# Patch_Panel.net
KiCad netlist of a schematic drawn in EAGLE
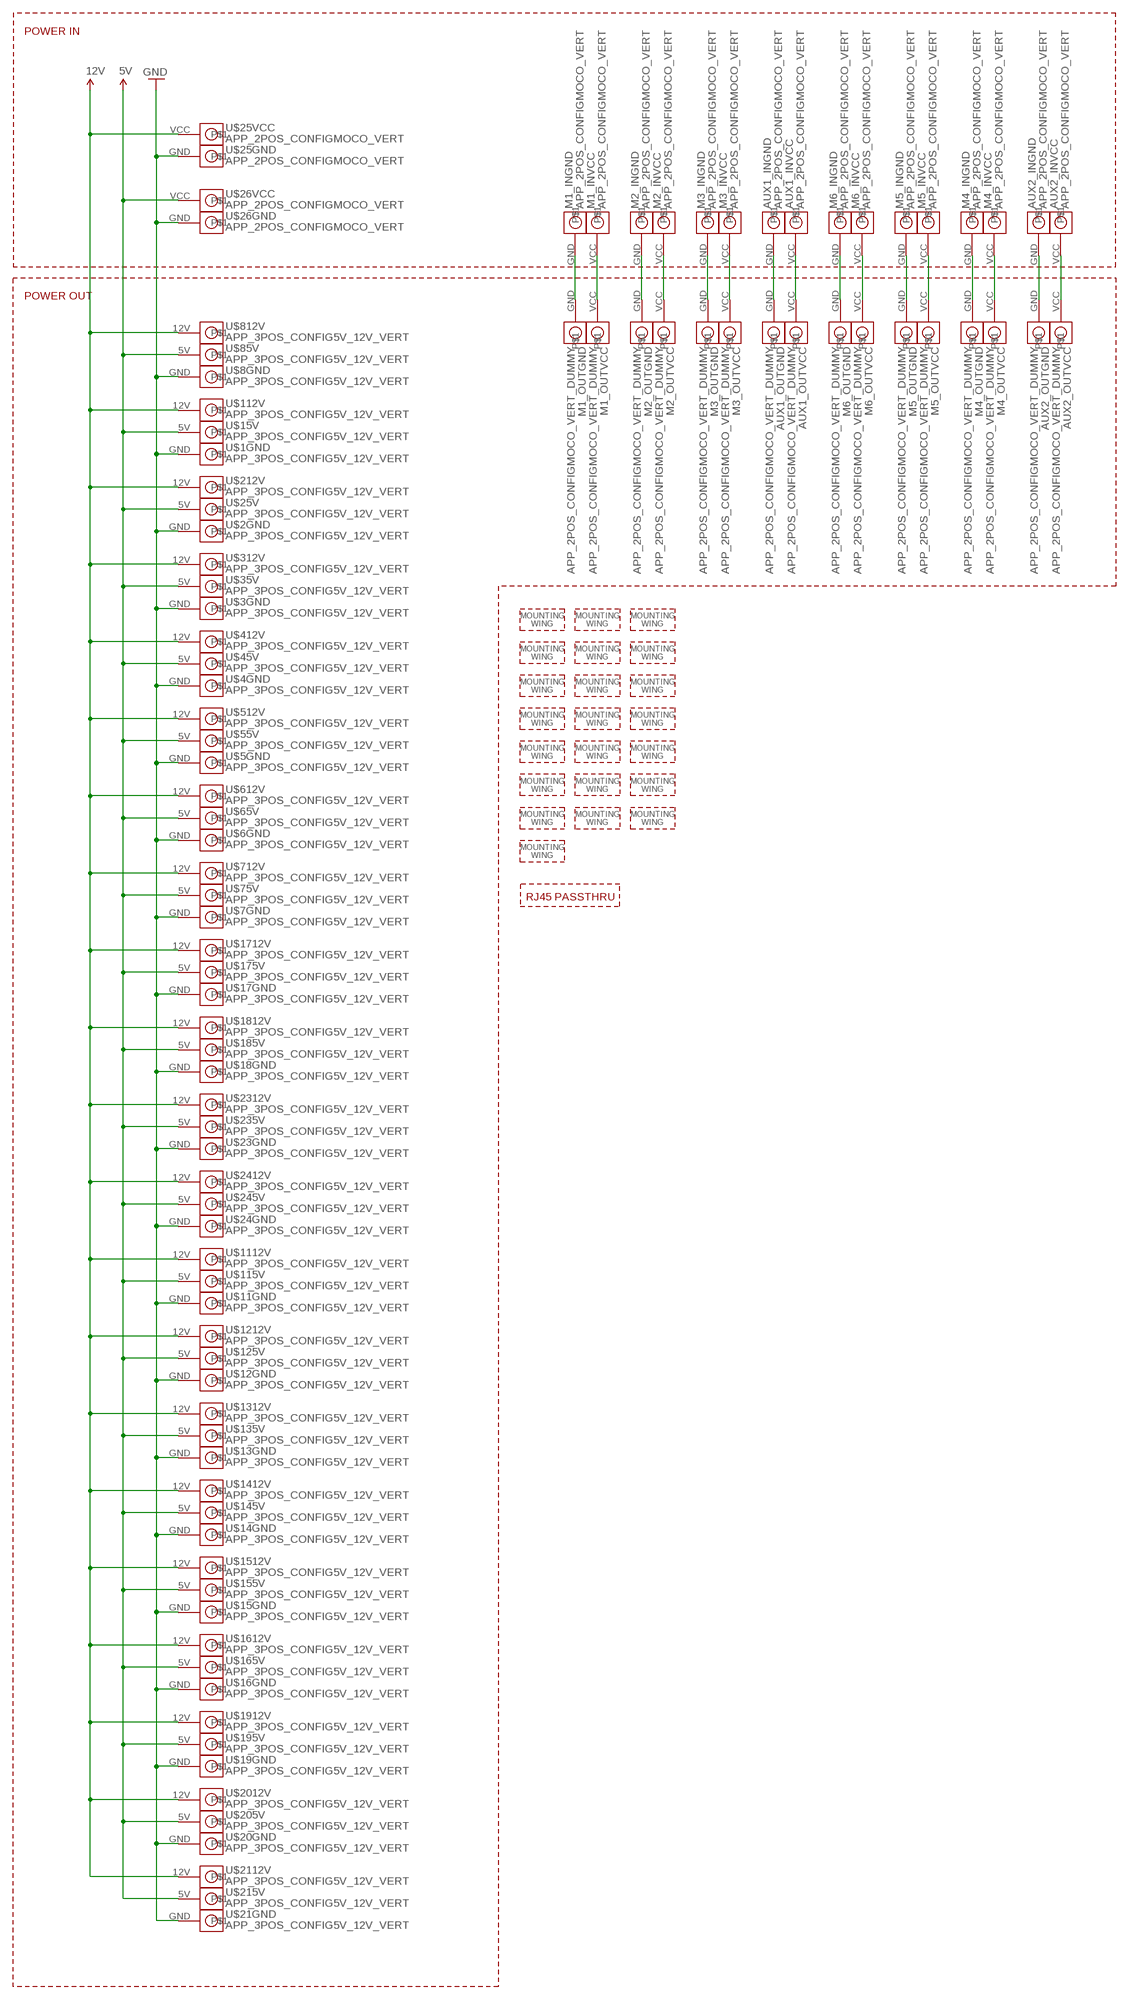
[diagram p0: schematic, sheet 1]

(export (version "E")
  (design (tool "Eeschema 10.0.6"))
  (components
    (comp (ref "AUX1_IN")
      (value "APP_2POS_CONFIGMOCO_VERT")
      (footprint "eagle-import:APP45_MOCO_VERT_CONFIG")
      (fields (field (name "COLOR1") "GREY"))
      (libsource (lib "eagle-import") (part "APP_2POS_CONFIGMOCO_VERT"))
    )
    (comp (ref "AUX1_OUT")
      (value "APP_2POS_CONFIGMOCO_VERT_DUMMY")
      (footprint "eagle-import:APP45_MOCO_VERT_CONFIG_DUMMY")
      (fields (field (name "COLOR1") "GREY"))
      (libsource (lib "eagle-import") (part "APP_2POS_CONFIGMOCO_VERT_DUMMY"))
    )
    (comp (ref "AUX2_IN")
      (value "APP_2POS_CONFIGMOCO_VERT")
      (footprint "eagle-import:APP45_MOCO_VERT_CONFIG")
      (fields (field (name "COLOR1") "GREY"))
      (libsource (lib "eagle-import") (part "APP_2POS_CONFIGMOCO_VERT"))
    )
    (comp (ref "AUX2_OUT")
      (value "APP_2POS_CONFIGMOCO_VERT_DUMMY")
      (footprint "eagle-import:APP45_MOCO_VERT_CONFIG_DUMMY")
      (fields (field (name "COLOR1") "GREY"))
      (libsource (lib "eagle-import") (part "APP_2POS_CONFIGMOCO_VERT_DUMMY"))
    )
    (comp (ref "M1_IN")
      (value "APP_2POS_CONFIGMOCO_VERT")
      (footprint "eagle-import:APP45_MOCO_VERT_CONFIG")
      (fields (field (name "COLOR1") "ORANGE"))
      (libsource (lib "eagle-import") (part "APP_2POS_CONFIGMOCO_VERT"))
    )
    (comp (ref "M1_OUT")
      (value "APP_2POS_CONFIGMOCO_VERT_DUMMY")
      (footprint "eagle-import:APP45_MOCO_VERT_CONFIG_DUMMY")
      (fields (field (name "COLOR1") "ORANGE"))
      (libsource (lib "eagle-import") (part "APP_2POS_CONFIGMOCO_VERT_DUMMY"))
    )
    (comp (ref "M2_IN")
      (value "APP_2POS_CONFIGMOCO_VERT")
      (footprint "eagle-import:APP45_MOCO_VERT_CONFIG")
      (fields (field (name "COLOR1") "WHITE"))
      (libsource (lib "eagle-import") (part "APP_2POS_CONFIGMOCO_VERT"))
    )
    (comp (ref "M2_OUT")
      (value "APP_2POS_CONFIGMOCO_VERT_DUMMY")
      (footprint "eagle-import:APP45_MOCO_VERT_CONFIG_DUMMY")
      (fields (field (name "COLOR1") "WHITE"))
      (libsource (lib "eagle-import") (part "APP_2POS_CONFIGMOCO_VERT_DUMMY"))
    )
    (comp (ref "M3_IN")
      (value "APP_2POS_CONFIGMOCO_VERT")
      (footprint "eagle-import:APP45_MOCO_VERT_CONFIG")
      (fields (field (name "COLOR1") "GREEN"))
      (libsource (lib "eagle-import") (part "APP_2POS_CONFIGMOCO_VERT"))
    )
    (comp (ref "M3_OUT")
      (value "APP_2POS_CONFIGMOCO_VERT_DUMMY")
      (footprint "eagle-import:APP45_MOCO_VERT_CONFIG_DUMMY")
      (fields (field (name "COLOR1") "GREEN"))
      (libsource (lib "eagle-import") (part "APP_2POS_CONFIGMOCO_VERT_DUMMY"))
    )
    (comp (ref "M4_IN")
      (value "APP_2POS_CONFIGMOCO_VERT")
      (footprint "eagle-import:APP45_MOCO_VERT_CONFIG")
      (fields (field (name "COLOR1") "PINK"))
      (libsource (lib "eagle-import") (part "APP_2POS_CONFIGMOCO_VERT"))
    )
    (comp (ref "M4_OUT")
      (value "APP_2POS_CONFIGMOCO_VERT_DUMMY")
      (footprint "eagle-import:APP45_MOCO_VERT_CONFIG_DUMMY")
      (fields (field (name "COLOR1") "PINK"))
      (libsource (lib "eagle-import") (part "APP_2POS_CONFIGMOCO_VERT_DUMMY"))
    )
    (comp (ref "M5_IN")
      (value "APP_2POS_CONFIGMOCO_VERT")
      (footprint "eagle-import:APP45_MOCO_VERT_CONFIG")
      (fields (field (name "COLOR1") "VIOLET"))
      (libsource (lib "eagle-import") (part "APP_2POS_CONFIGMOCO_VERT"))
    )
    (comp (ref "M5_OUT")
      (value "APP_2POS_CONFIGMOCO_VERT_DUMMY")
      (footprint "eagle-import:APP45_MOCO_VERT_CONFIG_DUMMY")
      (fields (field (name "COLOR1") "VIOLET"))
      (libsource (lib "eagle-import") (part "APP_2POS_CONFIGMOCO_VERT_DUMMY"))
    )
    (comp (ref "M6_IN")
      (value "APP_2POS_CONFIGMOCO_VERT")
      (footprint "eagle-import:APP45_MOCO_VERT_CONFIG")
      (fields (field (name "COLOR1") "BLUE"))
      (libsource (lib "eagle-import") (part "APP_2POS_CONFIGMOCO_VERT"))
    )
    (comp (ref "M6_OUT")
      (value "APP_2POS_CONFIGMOCO_VERT_DUMMY")
      (footprint "eagle-import:APP45_MOCO_VERT_CONFIG_DUMMY")
      (fields (field (name "COLOR1") "BLUE"))
      (libsource (lib "eagle-import") (part "APP_2POS_CONFIGMOCO_VERT_DUMMY"))
    )
    (comp (ref "U$1")
      (value "APP_3POS_CONFIG5V_12V_VERT")
      (footprint "eagle-import:APP45_5V_12V_VERT_CONFIG")
      (libsource (lib "eagle-import") (part "APP_3POS_CONFIG5V_12V_VERT"))
    )
    (comp (ref "U$2")
      (value "APP_3POS_CONFIG5V_12V_VERT")
      (footprint "eagle-import:APP45_5V_12V_VERT_CONFIG")
      (libsource (lib "eagle-import") (part "APP_3POS_CONFIG5V_12V_VERT"))
    )
    (comp (ref "U$3")
      (value "APP_3POS_CONFIG5V_12V_VERT")
      (footprint "eagle-import:APP45_5V_12V_VERT_CONFIG")
      (libsource (lib "eagle-import") (part "APP_3POS_CONFIG5V_12V_VERT"))
    )
    (comp (ref "U$4")
      (value "APP_3POS_CONFIG5V_12V_VERT")
      (footprint "eagle-import:APP45_5V_12V_VERT_CONFIG")
      (libsource (lib "eagle-import") (part "APP_3POS_CONFIG5V_12V_VERT"))
    )
    (comp (ref "U$5")
      (value "APP_3POS_CONFIG5V_12V_VERT")
      (footprint "eagle-import:APP45_5V_12V_VERT_CONFIG")
      (libsource (lib "eagle-import") (part "APP_3POS_CONFIG5V_12V_VERT"))
    )
    (comp (ref "U$6")
      (value "APP_3POS_CONFIG5V_12V_VERT")
      (footprint "eagle-import:APP45_5V_12V_VERT_CONFIG")
      (libsource (lib "eagle-import") (part "APP_3POS_CONFIG5V_12V_VERT"))
    )
    (comp (ref "U$7")
      (value "APP_3POS_CONFIG5V_12V_VERT")
      (footprint "eagle-import:APP45_5V_12V_VERT_CONFIG")
      (libsource (lib "eagle-import") (part "APP_3POS_CONFIG5V_12V_VERT"))
    )
    (comp (ref "U$8")
      (value "APP_3POS_CONFIG5V_12V_VERT")
      (footprint "eagle-import:APP45_5V_12V_VERT_CONFIG")
      (libsource (lib "eagle-import") (part "APP_3POS_CONFIG5V_12V_VERT"))
    )
    (comp (ref "U$9")
      (value "APP_MOUTING_WINGVERT")
      (footprint "eagle-import:APP45_MOUNTING_WING_VERT")
      (libsource (lib "eagle-import") (part "APP_MOUTING_WINGVERT"))
    )
    (comp (ref "U$10")
      (value "APP_MOUTING_WINGVERT")
      (footprint "eagle-import:APP45_MOUNTING_WING_VERT")
      (libsource (lib "eagle-import") (part "APP_MOUTING_WINGVERT"))
    )
    (comp (ref "U$11")
      (value "APP_3POS_CONFIG5V_12V_VERT")
      (footprint "eagle-import:APP45_5V_12V_VERT_CONFIG")
      (libsource (lib "eagle-import") (part "APP_3POS_CONFIG5V_12V_VERT"))
    )
    (comp (ref "U$12")
      (value "APP_3POS_CONFIG5V_12V_VERT")
      (footprint "eagle-import:APP45_5V_12V_VERT_CONFIG")
      (libsource (lib "eagle-import") (part "APP_3POS_CONFIG5V_12V_VERT"))
    )
    (comp (ref "U$13")
      (value "APP_3POS_CONFIG5V_12V_VERT")
      (footprint "eagle-import:APP45_5V_12V_VERT_CONFIG")
      (libsource (lib "eagle-import") (part "APP_3POS_CONFIG5V_12V_VERT"))
    )
    (comp (ref "U$14")
      (value "APP_3POS_CONFIG5V_12V_VERT")
      (footprint "eagle-import:APP45_5V_12V_VERT_CONFIG")
      (libsource (lib "eagle-import") (part "APP_3POS_CONFIG5V_12V_VERT"))
    )
    (comp (ref "U$15")
      (value "APP_3POS_CONFIG5V_12V_VERT")
      (footprint "eagle-import:APP45_5V_12V_VERT_CONFIG")
      (libsource (lib "eagle-import") (part "APP_3POS_CONFIG5V_12V_VERT"))
    )
    (comp (ref "U$16")
      (value "APP_3POS_CONFIG5V_12V_VERT")
      (footprint "eagle-import:APP45_5V_12V_VERT_CONFIG")
      (libsource (lib "eagle-import") (part "APP_3POS_CONFIG5V_12V_VERT"))
    )
    (comp (ref "U$17")
      (value "APP_3POS_CONFIG5V_12V_VERT")
      (footprint "eagle-import:APP45_5V_12V_VERT_CONFIG")
      (libsource (lib "eagle-import") (part "APP_3POS_CONFIG5V_12V_VERT"))
    )
    (comp (ref "U$18")
      (value "APP_3POS_CONFIG5V_12V_VERT")
      (footprint "eagle-import:APP45_5V_12V_VERT_CONFIG")
      (libsource (lib "eagle-import") (part "APP_3POS_CONFIG5V_12V_VERT"))
    )
    (comp (ref "U$19")
      (value "APP_3POS_CONFIG5V_12V_VERT")
      (footprint "eagle-import:APP45_5V_12V_VERT_CONFIG")
      (libsource (lib "eagle-import") (part "APP_3POS_CONFIG5V_12V_VERT"))
    )
    (comp (ref "U$20")
      (value "APP_3POS_CONFIG5V_12V_VERT")
      (footprint "eagle-import:APP45_5V_12V_VERT_CONFIG")
      (libsource (lib "eagle-import") (part "APP_3POS_CONFIG5V_12V_VERT"))
    )
    (comp (ref "U$21")
      (value "APP_3POS_CONFIG5V_12V_VERT")
      (footprint "eagle-import:APP45_5V_12V_VERT_CONFIG")
      (libsource (lib "eagle-import") (part "APP_3POS_CONFIG5V_12V_VERT"))
    )
    (comp (ref "U$22")
      (value "APP_MOUTING_WINGVERT")
      (footprint "eagle-import:APP45_MOUNTING_WING_VERT")
      (libsource (lib "eagle-import") (part "APP_MOUTING_WINGVERT"))
    )
    (comp (ref "U$23")
      (value "APP_3POS_CONFIG5V_12V_VERT")
      (footprint "eagle-import:APP45_5V_12V_VERT_CONFIG")
      (libsource (lib "eagle-import") (part "APP_3POS_CONFIG5V_12V_VERT"))
    )
    (comp (ref "U$24")
      (value "APP_3POS_CONFIG5V_12V_VERT")
      (footprint "eagle-import:APP45_5V_12V_VERT_CONFIG")
      (libsource (lib "eagle-import") (part "APP_3POS_CONFIG5V_12V_VERT"))
    )
    (comp (ref "U$25")
      (value "APP_2POS_CONFIGMOCO_VERT")
      (footprint "eagle-import:APP45_MOCO_VERT_CONFIG")
      (libsource (lib "eagle-import") (part "APP_2POS_CONFIGMOCO_VERT"))
    )
    (comp (ref "U$26")
      (value "APP_2POS_CONFIGMOCO_VERT")
      (footprint "eagle-import:APP45_MOCO_VERT_CONFIG")
      (libsource (lib "eagle-import") (part "APP_2POS_CONFIGMOCO_VERT"))
    )
    (comp (ref "U$27")
      (value "APP_MOUTING_WINGVERT")
      (footprint "eagle-import:APP45_MOUNTING_WING_VERT")
      (libsource (lib "eagle-import") (part "APP_MOUTING_WINGVERT"))
    )
    (comp (ref "U$28")
      (value "APP_MOUTING_WINGVERT")
      (footprint "eagle-import:APP45_MOUNTING_WING_VERT")
      (libsource (lib "eagle-import") (part "APP_MOUTING_WINGVERT"))
    )
    (comp (ref "U$29")
      (value "APP_MOUTING_WINGVERT")
      (footprint "eagle-import:APP45_MOUNTING_WING_VERT")
      (libsource (lib "eagle-import") (part "APP_MOUTING_WINGVERT"))
    )
    (comp (ref "U$30")
      (value "APP_MOUTING_WINGVERT")
      (footprint "eagle-import:APP45_MOUNTING_WING_VERT")
      (libsource (lib "eagle-import") (part "APP_MOUTING_WINGVERT"))
    )
    (comp (ref "U$31")
      (value "APP_MOUTING_WINGVERT")
      (footprint "eagle-import:APP45_MOUNTING_WING_VERT")
      (libsource (lib "eagle-import") (part "APP_MOUTING_WINGVERT"))
    )
    (comp (ref "U$32")
      (value "APP_MOUTING_WINGVERT")
      (footprint "eagle-import:APP45_MOUNTING_WING_VERT")
      (libsource (lib "eagle-import") (part "APP_MOUTING_WINGVERT"))
    )
    (comp (ref "U$33")
      (value "APP_MOUTING_WINGVERT")
      (footprint "eagle-import:APP45_MOUNTING_WING_VERT")
      (libsource (lib "eagle-import") (part "APP_MOUTING_WINGVERT"))
    )
    (comp (ref "U$34")
      (value "APP_MOUTING_WINGVERT")
      (footprint "eagle-import:APP45_MOUNTING_WING_VERT")
      (libsource (lib "eagle-import") (part "APP_MOUTING_WINGVERT"))
    )
    (comp (ref "U$35")
      (value "APP_MOUTING_WINGVERT")
      (footprint "eagle-import:APP45_MOUNTING_WING_VERT")
      (libsource (lib "eagle-import") (part "APP_MOUTING_WINGVERT"))
    )
    (comp (ref "U$36")
      (value "APP_MOUTING_WINGVERT")
      (footprint "eagle-import:APP45_MOUNTING_WING_VERT")
      (libsource (lib "eagle-import") (part "APP_MOUTING_WINGVERT"))
    )
    (comp (ref "U$37")
      (value "APP_MOUTING_WINGVERT")
      (footprint "eagle-import:APP45_MOUNTING_WING_VERT")
      (libsource (lib "eagle-import") (part "APP_MOUTING_WINGVERT"))
    )
    (comp (ref "U$38")
      (value "APP_MOUTING_WINGVERT")
      (footprint "eagle-import:APP45_MOUNTING_WING_VERT")
      (libsource (lib "eagle-import") (part "APP_MOUTING_WINGVERT"))
    )
    (comp (ref "U$39")
      (value "APP_MOUTING_WINGVERT")
      (footprint "eagle-import:APP45_MOUNTING_WING_VERT")
      (libsource (lib "eagle-import") (part "APP_MOUTING_WINGVERT"))
    )
    (comp (ref "U$40")
      (value "APP_MOUTING_WINGVERT")
      (footprint "eagle-import:APP45_MOUNTING_WING_VERT")
      (libsource (lib "eagle-import") (part "APP_MOUTING_WINGVERT"))
    )
    (comp (ref "U$41")
      (value "APP_MOUTING_WINGVERT")
      (footprint "eagle-import:APP45_MOUNTING_WING_VERT")
      (libsource (lib "eagle-import") (part "APP_MOUTING_WINGVERT"))
    )
    (comp (ref "U$42")
      (value "APP_MOUTING_WINGVERT")
      (footprint "eagle-import:APP45_MOUNTING_WING_VERT")
      (libsource (lib "eagle-import") (part "APP_MOUTING_WINGVERT"))
    )
    (comp (ref "U$43")
      (value "APP_MOUTING_WINGVERT")
      (footprint "eagle-import:APP45_MOUNTING_WING_VERT")
      (libsource (lib "eagle-import") (part "APP_MOUTING_WINGVERT"))
    )
    (comp (ref "U$44")
      (value "APP_MOUTING_WINGVERT")
      (footprint "eagle-import:APP45_MOUNTING_WING_VERT")
      (libsource (lib "eagle-import") (part "APP_MOUTING_WINGVERT"))
    )
    (comp (ref "U$45")
      (value "APP_MOUTING_WINGVERT")
      (footprint "eagle-import:APP45_MOUNTING_WING_VERT")
      (libsource (lib "eagle-import") (part "APP_MOUTING_WINGVERT"))
    )
    (comp (ref "U$46")
      (value "RJ45_PASSTHRUMRDT_MALE_RJ45_STANDOFF")
      (footprint "eagle-import:MRDT_MALE_RJ45_STANDOFF")
      (libsource (lib "eagle-import") (part "RJ45_PASSTHRUMRDT_MALE_RJ45_STANDOFF"))
    )
  )
  (nets
    (net (code "1") (name "5V") (class "Default")
      (node (ref "U$1") (pin "5V") (pinfunction "P$1_5V") (pintype "bidirectional"))
      (node (ref "U$11") (pin "5V") (pinfunction "P$1_5V") (pintype "bidirectional"))
      (node (ref "U$12") (pin "5V") (pinfunction "P$1_5V") (pintype "bidirectional"))
      (node (ref "U$13") (pin "5V") (pinfunction "P$1_5V") (pintype "bidirectional"))
      (node (ref "U$14") (pin "5V") (pinfunction "P$1_5V") (pintype "bidirectional"))
      (node (ref "U$15") (pin "5V") (pinfunction "P$1_5V") (pintype "bidirectional"))
      (node (ref "U$16") (pin "5V") (pinfunction "P$1_5V") (pintype "bidirectional"))
      (node (ref "U$17") (pin "5V") (pinfunction "P$1_5V") (pintype "bidirectional"))
      (node (ref "U$18") (pin "5V") (pinfunction "P$1_5V") (pintype "bidirectional"))
      (node (ref "U$19") (pin "5V") (pinfunction "P$1_5V") (pintype "bidirectional"))
      (node (ref "U$2") (pin "5V") (pinfunction "P$1_5V") (pintype "bidirectional"))
      (node (ref "U$20") (pin "5V") (pinfunction "P$1_5V") (pintype "bidirectional"))
      (node (ref "U$21") (pin "5V") (pinfunction "P$1_5V") (pintype "bidirectional"))
      (node (ref "U$23") (pin "5V") (pinfunction "P$1_5V") (pintype "bidirectional"))
      (node (ref "U$24") (pin "5V") (pinfunction "P$1_5V") (pintype "bidirectional"))
      (node (ref "U$26") (pin "VCC") (pinfunction "P$1_VCC") (pintype "bidirectional"))
      (node (ref "U$3") (pin "5V") (pinfunction "P$1_5V") (pintype "bidirectional"))
      (node (ref "U$4") (pin "5V") (pinfunction "P$1_5V") (pintype "bidirectional"))
      (node (ref "U$5") (pin "5V") (pinfunction "P$1_5V") (pintype "bidirectional"))
      (node (ref "U$6") (pin "5V") (pinfunction "P$1_5V") (pintype "bidirectional"))
      (node (ref "U$7") (pin "5V") (pinfunction "P$1_5V") (pintype "bidirectional"))
      (node (ref "U$8") (pin "5V") (pinfunction "P$1_5V") (pintype "bidirectional"))
    )
    (net (code "2") (name "12V") (class "Default")
      (node (ref "U$1") (pin "12V") (pinfunction "P$1_12V") (pintype "bidirectional"))
      (node (ref "U$11") (pin "12V") (pinfunction "P$1_12V") (pintype "bidirectional"))
      (node (ref "U$12") (pin "12V") (pinfunction "P$1_12V") (pintype "bidirectional"))
      (node (ref "U$13") (pin "12V") (pinfunction "P$1_12V") (pintype "bidirectional"))
      (node (ref "U$14") (pin "12V") (pinfunction "P$1_12V") (pintype "bidirectional"))
      (node (ref "U$15") (pin "12V") (pinfunction "P$1_12V") (pintype "bidirectional"))
      (node (ref "U$16") (pin "12V") (pinfunction "P$1_12V") (pintype "bidirectional"))
      (node (ref "U$17") (pin "12V") (pinfunction "P$1_12V") (pintype "bidirectional"))
      (node (ref "U$18") (pin "12V") (pinfunction "P$1_12V") (pintype "bidirectional"))
      (node (ref "U$19") (pin "12V") (pinfunction "P$1_12V") (pintype "bidirectional"))
      (node (ref "U$2") (pin "12V") (pinfunction "P$1_12V") (pintype "bidirectional"))
      (node (ref "U$20") (pin "12V") (pinfunction "P$1_12V") (pintype "bidirectional"))
      (node (ref "U$21") (pin "12V") (pinfunction "P$1_12V") (pintype "bidirectional"))
      (node (ref "U$23") (pin "12V") (pinfunction "P$1_12V") (pintype "bidirectional"))
      (node (ref "U$24") (pin "12V") (pinfunction "P$1_12V") (pintype "bidirectional"))
      (node (ref "U$25") (pin "VCC") (pinfunction "P$1_VCC") (pintype "bidirectional"))
      (node (ref "U$3") (pin "12V") (pinfunction "P$1_12V") (pintype "bidirectional"))
      (node (ref "U$4") (pin "12V") (pinfunction "P$1_12V") (pintype "bidirectional"))
      (node (ref "U$5") (pin "12V") (pinfunction "P$1_12V") (pintype "bidirectional"))
      (node (ref "U$6") (pin "12V") (pinfunction "P$1_12V") (pintype "bidirectional"))
      (node (ref "U$7") (pin "12V") (pinfunction "P$1_12V") (pintype "bidirectional"))
      (node (ref "U$8") (pin "12V") (pinfunction "P$1_12V") (pintype "bidirectional"))
    )
    (net (code "3") (name "GND") (class "Default")
      (node (ref "AUX1_IN") (pin "GND") (pinfunction "P$1_GND") (pintype "bidirectional"))
      (node (ref "AUX1_OUT") (pin "GND") (pinfunction "P$1_GND") (pintype "bidirectional"))
      (node (ref "AUX2_IN") (pin "GND") (pinfunction "P$1_GND") (pintype "bidirectional"))
      (node (ref "AUX2_OUT") (pin "GND") (pinfunction "P$1_GND") (pintype "bidirectional"))
      (node (ref "M1_IN") (pin "GND") (pinfunction "P$1_GND") (pintype "bidirectional"))
      (node (ref "M1_OUT") (pin "GND") (pinfunction "P$1_GND") (pintype "bidirectional"))
      (node (ref "M2_IN") (pin "GND") (pinfunction "P$1_GND") (pintype "bidirectional"))
      (node (ref "M2_OUT") (pin "GND") (pinfunction "P$1_GND") (pintype "bidirectional"))
      (node (ref "M3_IN") (pin "GND") (pinfunction "P$1_GND") (pintype "bidirectional"))
      (node (ref "M3_OUT") (pin "GND") (pinfunction "P$1_GND") (pintype "bidirectional"))
      (node (ref "M4_IN") (pin "GND") (pinfunction "P$1_GND") (pintype "bidirectional"))
      (node (ref "M4_OUT") (pin "GND") (pinfunction "P$1_GND") (pintype "bidirectional"))
      (node (ref "M5_IN") (pin "GND") (pinfunction "P$1_GND") (pintype "bidirectional"))
      (node (ref "M5_OUT") (pin "GND") (pinfunction "P$1_GND") (pintype "bidirectional"))
      (node (ref "M6_IN") (pin "GND") (pinfunction "P$1_GND") (pintype "bidirectional"))
      (node (ref "M6_OUT") (pin "GND") (pinfunction "P$1_GND") (pintype "bidirectional"))
      (node (ref "U$1") (pin "GND") (pinfunction "P$1_GND") (pintype "bidirectional"))
      (node (ref "U$11") (pin "GND") (pinfunction "P$1_GND") (pintype "bidirectional"))
      (node (ref "U$12") (pin "GND") (pinfunction "P$1_GND") (pintype "bidirectional"))
      (node (ref "U$13") (pin "GND") (pinfunction "P$1_GND") (pintype "bidirectional"))
      (node (ref "U$14") (pin "GND") (pinfunction "P$1_GND") (pintype "bidirectional"))
      (node (ref "U$15") (pin "GND") (pinfunction "P$1_GND") (pintype "bidirectional"))
      (node (ref "U$16") (pin "GND") (pinfunction "P$1_GND") (pintype "bidirectional"))
      (node (ref "U$17") (pin "GND") (pinfunction "P$1_GND") (pintype "bidirectional"))
      (node (ref "U$18") (pin "GND") (pinfunction "P$1_GND") (pintype "bidirectional"))
      (node (ref "U$19") (pin "GND") (pinfunction "P$1_GND") (pintype "bidirectional"))
      (node (ref "U$2") (pin "GND") (pinfunction "P$1_GND") (pintype "bidirectional"))
      (node (ref "U$20") (pin "GND") (pinfunction "P$1_GND") (pintype "bidirectional"))
      (node (ref "U$21") (pin "GND") (pinfunction "P$1_GND") (pintype "bidirectional"))
      (node (ref "U$23") (pin "GND") (pinfunction "P$1_GND") (pintype "bidirectional"))
      (node (ref "U$24") (pin "GND") (pinfunction "P$1_GND") (pintype "bidirectional"))
      (node (ref "U$25") (pin "GND") (pinfunction "P$1_GND") (pintype "bidirectional"))
      (node (ref "U$26") (pin "GND") (pinfunction "P$1_GND") (pintype "bidirectional"))
      (node (ref "U$3") (pin "GND") (pinfunction "P$1_GND") (pintype "bidirectional"))
      (node (ref "U$4") (pin "GND") (pinfunction "P$1_GND") (pintype "bidirectional"))
      (node (ref "U$5") (pin "GND") (pinfunction "P$1_GND") (pintype "bidirectional"))
      (node (ref "U$6") (pin "GND") (pinfunction "P$1_GND") (pintype "bidirectional"))
      (node (ref "U$7") (pin "GND") (pinfunction "P$1_GND") (pintype "bidirectional"))
      (node (ref "U$8") (pin "GND") (pinfunction "P$1_GND") (pintype "bidirectional"))
    )
    (net (code "4") (name "Net-(AUX1_INB-P$1)") (class "Default")
      (node (ref "AUX1_IN") (pin "VCC") (pinfunction "P$1_VCC") (pintype "bidirectional"))
      (node (ref "AUX1_OUT") (pin "VCC") (pinfunction "P$1_VCC") (pintype "bidirectional"))
    )
    (net (code "5") (name "Net-(AUX2_INB-P$1)") (class "Default")
      (node (ref "AUX2_IN") (pin "VCC") (pinfunction "P$1_VCC") (pintype "bidirectional"))
      (node (ref "AUX2_OUT") (pin "VCC") (pinfunction "P$1_VCC") (pintype "bidirectional"))
    )
    (net (code "6") (name "Net-(M1_INB-P$1)") (class "Default")
      (node (ref "M1_IN") (pin "VCC") (pinfunction "P$1_VCC") (pintype "bidirectional"))
      (node (ref "M1_OUT") (pin "VCC") (pinfunction "P$1_VCC") (pintype "bidirectional"))
    )
    (net (code "7") (name "Net-(M2_INB-P$1)") (class "Default")
      (node (ref "M2_IN") (pin "VCC") (pinfunction "P$1_VCC") (pintype "bidirectional"))
      (node (ref "M2_OUT") (pin "VCC") (pinfunction "P$1_VCC") (pintype "bidirectional"))
    )
    (net (code "8") (name "Net-(M3_INB-P$1)") (class "Default")
      (node (ref "M3_IN") (pin "VCC") (pinfunction "P$1_VCC") (pintype "bidirectional"))
      (node (ref "M3_OUT") (pin "VCC") (pinfunction "P$1_VCC") (pintype "bidirectional"))
    )
    (net (code "9") (name "Net-(M4_INB-P$1)") (class "Default")
      (node (ref "M4_IN") (pin "VCC") (pinfunction "P$1_VCC") (pintype "bidirectional"))
      (node (ref "M4_OUT") (pin "VCC") (pinfunction "P$1_VCC") (pintype "bidirectional"))
    )
    (net (code "10") (name "Net-(M5_INB-P$1)") (class "Default")
      (node (ref "M5_IN") (pin "VCC") (pinfunction "P$1_VCC") (pintype "bidirectional"))
      (node (ref "M5_OUT") (pin "VCC") (pinfunction "P$1_VCC") (pintype "bidirectional"))
    )
    (net (code "11") (name "Net-(M6_INB-P$1)") (class "Default")
      (node (ref "M6_IN") (pin "VCC") (pinfunction "P$1_VCC") (pintype "bidirectional"))
      (node (ref "M6_OUT") (pin "VCC") (pinfunction "P$1_VCC") (pintype "bidirectional"))
    )
  )
)
